# DMB.net
KiCad netlist of a schematic drawn in Altium Designer
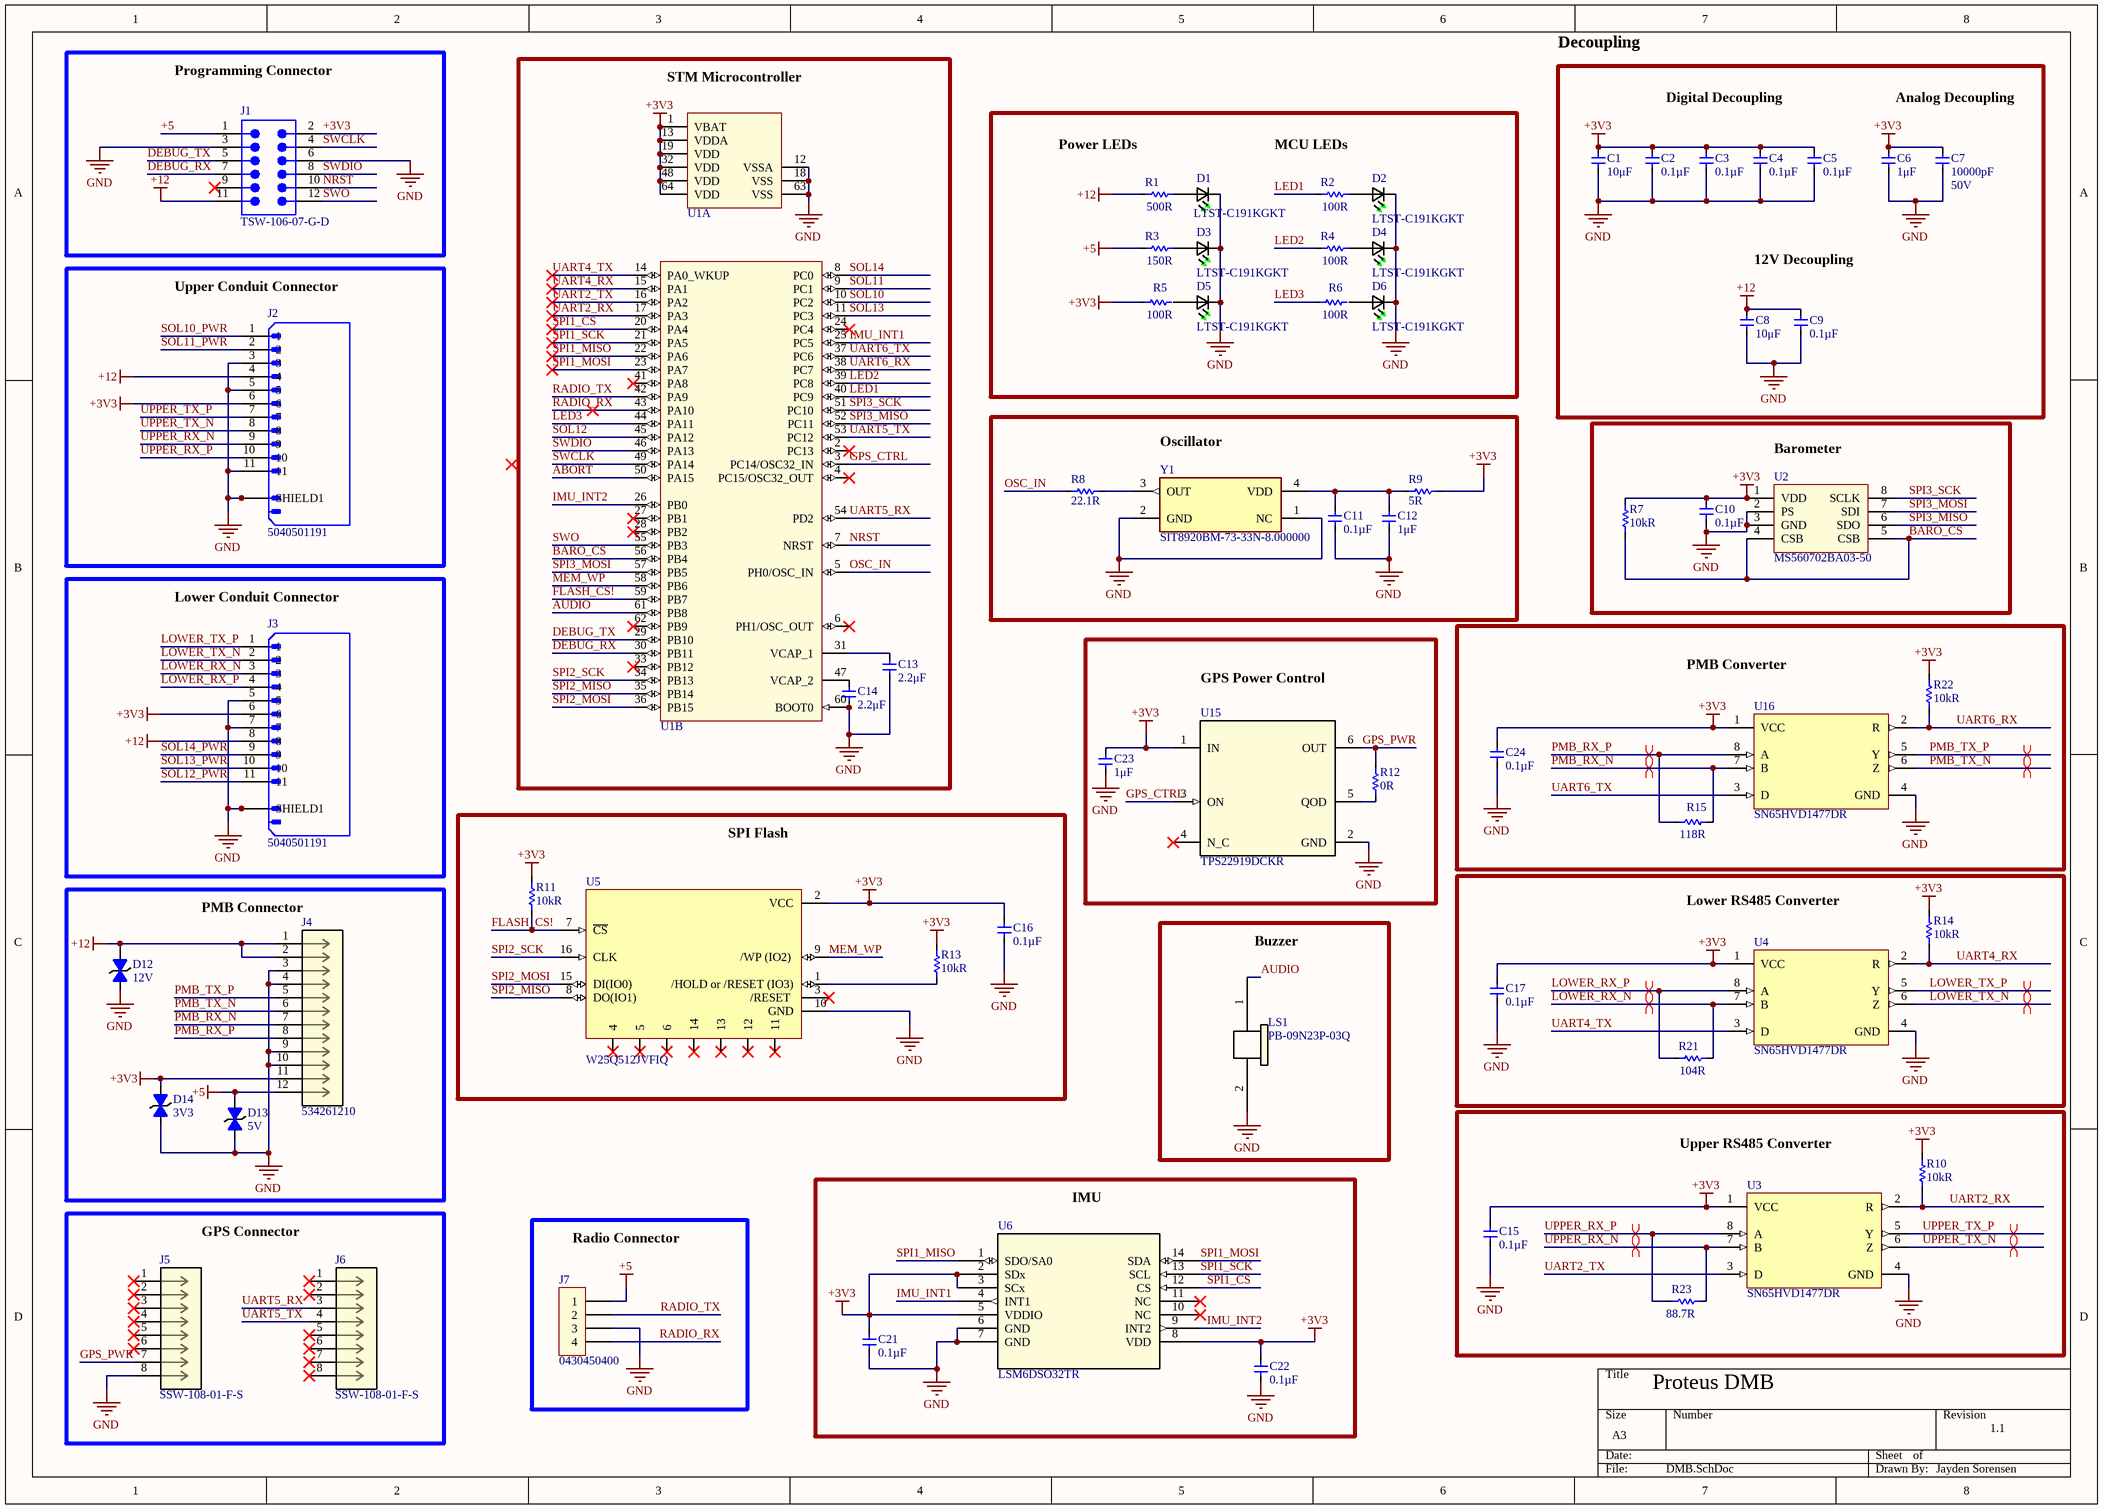
[diagram p0: DMB.SchDoc]

(export (version "E")
  (design (tool "Eeschema 10.0.6"))
  (components
    (comp (ref "C1")
      (value "10μF")
      (footprint "0603")
      (description "CAP CER 10UF 10V X5R 0603")
      (libsource (lib "BioRocketSchematics") (part "CL10A106MP8NNNC"))
    )
    (comp (ref "C2")
      (value "CGA3E2X7R1E104K080AA")
      (footprint "0603")
      (description "CAP CER 0.1UF 25V X7R 0603")
      (fields
        (field (name "MANUFACTURER") "TDK Corporation")
        (field (name "TOLERANCE") "±10%")
        (field (name "CAPACITANCE") "0.1µF")
      )
      (libsource (lib "BioRocketSchematics") (part "CGA3E2X7R1E104K080AA"))
    )
    (comp (ref "C3")
      (value "CGA3E2X7R1E104K080AA")
      (footprint "0603")
      (description "CAP CER 0.1UF 25V X7R 0603")
      (fields
        (field (name "MANUFACTURER") "TDK Corporation")
        (field (name "TOLERANCE") "±10%")
        (field (name "CAPACITANCE") "0.1µF")
      )
      (libsource (lib "BioRocketSchematics") (part "CGA3E2X7R1E104K080AA"))
    )
    (comp (ref "C4")
      (value "CGA3E2X7R1E104K080AA")
      (footprint "0603")
      (description "CAP CER 0.1UF 25V X7R 0603")
      (fields
        (field (name "MANUFACTURER") "TDK Corporation")
        (field (name "TOLERANCE") "±10%")
        (field (name "CAPACITANCE") "0.1µF")
      )
      (libsource (lib "BioRocketSchematics") (part "CGA3E2X7R1E104K080AA"))
    )
    (comp (ref "C5")
      (value "CGA3E2X7R1E104K080AA")
      (footprint "0603")
      (description "CAP CER 0.1UF 25V X7R 0603")
      (fields
        (field (name "MANUFACTURER") "TDK Corporation")
        (field (name "TOLERANCE") "±10%")
        (field (name "CAPACITANCE") "0.1µF")
      )
      (libsource (lib "BioRocketSchematics") (part "CGA3E2X7R1E104K080AA"))
    )
    (comp (ref "C6")
      (value "1μF")
      (footprint "0603")
      (description "CAP CER 1UF 10V X5R 0603")
      (libsource (lib "BioRocketSchematics") (part "CL10A105KP8NNNC"))
    )
    (comp (ref "C7")
      (value "CGA3E2X7R1H103K080AA")
      (footprint "0603")
      (description "CAP CER 10000PF 50V X7R 0603")
      (fields
        (field (name "MANUFACTURER") "TDK Corporation")
        (field (name "TOLERANCE") "±10%")
        (field (name "CAPACITANCE") "10000pF")
        (field (name "VOLTAGE - RATED") "50V")
      )
      (libsource (lib "BioRocketSchematics") (part "CGA3E2X7R1H103K080AA"))
    )
    (comp (ref "C8")
      (value "10μF")
      (footprint "0603")
      (description "CAP CER 10UF 10V X5R 0603")
      (libsource (lib "BioRocketSchematics") (part "CL10A106MP8NNNC"))
    )
    (comp (ref "C9")
      (value "CGA3E2X7R1E104K080AA")
      (footprint "0603")
      (description "CAP CER 0.1UF 25V X7R 0603")
      (fields
        (field (name "MANUFACTURER") "TDK Corporation")
        (field (name "TOLERANCE") "±10%")
        (field (name "CAPACITANCE") "0.1µF")
      )
      (libsource (lib "BioRocketSchematics") (part "CGA3E2X7R1E104K080AA"))
    )
    (comp (ref "C10")
      (value "CGA3E2X7R1E104K080AA")
      (footprint "0603")
      (description "CAP CER 0.1UF 25V X7R 0603")
      (fields
        (field (name "MANUFACTURER") "TDK Corporation")
        (field (name "TOLERANCE") "±10%")
        (field (name "CAPACITANCE") "0.1µF")
      )
      (libsource (lib "BioRocketSchematics") (part "CGA3E2X7R1E104K080AA"))
    )
    (comp (ref "C11")
      (value "CGA3E2X7R1E104K080AA")
      (footprint "0603")
      (description "CAP CER 0.1UF 25V X7R 0603")
      (fields
        (field (name "MANUFACTURER") "TDK Corporation")
        (field (name "TOLERANCE") "±10%")
        (field (name "CAPACITANCE") "0.1µF")
      )
      (libsource (lib "BioRocketSchematics") (part "CGA3E2X7R1E104K080AA"))
    )
    (comp (ref "C12")
      (value "1μF")
      (footprint "0603")
      (description "CAP CER 1UF 10V X5R 0603")
      (libsource (lib "BioRocketSchematics") (part "CL10A105KP8NNNC"))
    )
    (comp (ref "C13")
      (value "2.2μF")
      (footprint "0603")
      (description "CAP CER 2.2UF 16V X5R 0603")
      (libsource (lib "BioRocketSchematics") (part "C1608X5R1C225K080AB"))
    )
    (comp (ref "C14")
      (value "2.2μF")
      (footprint "0603")
      (description "CAP CER 2.2UF 16V X5R 0603")
      (libsource (lib "BioRocketSchematics") (part "C1608X5R1C225K080AB"))
    )
    (comp (ref "C15")
      (value "CGA3E2X7R1E104K080AA")
      (footprint "0603")
      (description "CAP CER 0.1UF 25V X7R 0603")
      (fields
        (field (name "MANUFACTURER") "TDK Corporation")
        (field (name "TOLERANCE") "±10%")
        (field (name "CAPACITANCE") "0.1µF")
      )
      (libsource (lib "BioRocketSchematics") (part "CGA3E2X7R1E104K080AA"))
    )
    (comp (ref "C16")
      (value "CGA3E2X7R1E104K080AA")
      (footprint "0603")
      (description "CAP CER 0.1UF 25V X7R 0603")
      (fields
        (field (name "MANUFACTURER") "TDK Corporation")
        (field (name "TOLERANCE") "±10%")
        (field (name "CAPACITANCE") "0.1µF")
      )
      (libsource (lib "BioRocketSchematics") (part "CGA3E2X7R1E104K080AA"))
    )
    (comp (ref "C17")
      (value "CGA3E2X7R1E104K080AA")
      (footprint "0603")
      (description "CAP CER 0.1UF 25V X7R 0603")
      (fields
        (field (name "MANUFACTURER") "TDK Corporation")
        (field (name "TOLERANCE") "±10%")
        (field (name "CAPACITANCE") "0.1µF")
      )
      (libsource (lib "BioRocketSchematics") (part "CGA3E2X7R1E104K080AA"))
    )
    (comp (ref "C21")
      (value "CGA3E2X7R1E104K080AA")
      (footprint "0603")
      (description "CAP CER 0.1UF 25V X7R 0603")
      (fields
        (field (name "MANUFACTURER") "TDK Corporation")
        (field (name "TOLERANCE") "±10%")
        (field (name "CAPACITANCE") "0.1µF")
      )
      (libsource (lib "BioRocketSchematics") (part "CGA3E2X7R1E104K080AA"))
    )
    (comp (ref "C22")
      (value "CGA3E2X7R1E104K080AA")
      (footprint "0603")
      (description "CAP CER 0.1UF 25V X7R 0603")
      (fields
        (field (name "MANUFACTURER") "TDK Corporation")
        (field (name "TOLERANCE") "±10%")
        (field (name "CAPACITANCE") "0.1µF")
      )
      (libsource (lib "BioRocketSchematics") (part "CGA3E2X7R1E104K080AA"))
    )
    (comp (ref "C23")
      (value "1μF")
      (footprint "0603")
      (description "CAP CER 1UF 10V X5R 0603")
      (libsource (lib "BioRocketSchematics") (part "CL10A105KP8NNNC"))
    )
    (comp (ref "C24")
      (value "CGA3E2X7R1E104K080AA")
      (footprint "0603")
      (description "CAP CER 0.1UF 25V X7R 0603")
      (fields
        (field (name "MANUFACTURER") "TDK Corporation")
        (field (name "TOLERANCE") "±10%")
        (field (name "CAPACITANCE") "0.1µF")
      )
      (libsource (lib "BioRocketSchematics") (part "CGA3E2X7R1E104K080AA"))
    )
    (comp (ref "D1")
      (value "LTST-C191KGKT")
      (footprint "LED_LTST-C191KGKT_LTO")
      (description "LED GREEN CLEAR SMD 0603")
      (libsource (lib "BioRocketSchematics") (part "LTST-C191KGKT"))
    )
    (comp (ref "D2")
      (value "LTST-C191KGKT")
      (footprint "LED_LTST-C191KGKT_LTO")
      (description "LED GREEN CLEAR SMD 0603")
      (libsource (lib "BioRocketSchematics") (part "LTST-C191KGKT"))
    )
    (comp (ref "D3")
      (value "LTST-C191KGKT")
      (footprint "LED_LTST-C191KGKT_LTO")
      (description "LED GREEN CLEAR SMD 0603")
      (libsource (lib "BioRocketSchematics") (part "LTST-C191KGKT"))
    )
    (comp (ref "D4")
      (value "LTST-C191KGKT")
      (footprint "LED_LTST-C191KGKT_LTO")
      (description "LED GREEN CLEAR SMD 0603")
      (libsource (lib "BioRocketSchematics") (part "LTST-C191KGKT"))
    )
    (comp (ref "D5")
      (value "LTST-C191KGKT")
      (footprint "LED_LTST-C191KGKT_LTO")
      (description "LED GREEN CLEAR SMD 0603")
      (libsource (lib "BioRocketSchematics") (part "LTST-C191KGKT"))
    )
    (comp (ref "D6")
      (value "LTST-C191KGKT")
      (footprint "LED_LTST-C191KGKT_LTO")
      (description "LED GREEN CLEAR SMD 0603")
      (libsource (lib "BioRocketSchematics") (part "LTST-C191KGKT"))
    )
    (comp (ref "D12")
      (value "12V")
      (footprint "SOD-323-2")
      (description "TVS 12V Working, 23V Clamp - ESD Suppressor Diode TVS Bi-Dir 12V Automotive 2-Pin SOD-323 T/R")
      (fields
        (field (name "MANUFACTURER") "Littelfuse")
        (field (name "MANUFACTURER PART NUMBER") "SD12C-01FTG")
      )
      (libsource (lib "BioRocketSchematics") (part "SD12C-01FTG"))
    )
    (comp (ref "D13")
      (value "5V")
      (footprint "SOD-323-2")
      (description "TVS 5V Working, 19.6V Clamp - ESD Protection Diodes / TVS Diodes 2.5pF 25A BI for Surge Protection")
      (libsource (lib "BioRocketSchematics") (part "SP4021-01FTG-C"))
    )
    (comp (ref "D14")
      (value "3V3")
      (footprint "SOD-323-2")
      (description "TVS 3.3V Working, 10.9V Clamp - 10.9V (Typ) Clamp 43A (8/20µs) Ipp Tvs Diode Surface Mount SOD-323")
      (fields
        (field (name "MANUFACTURER") "Bourns")
        (field (name "MANUFACTURER PART NUMBER") "CDSOD323-T03SC")
      )
      (libsource (lib "BioRocketSchematics") (part "CDSOD323-T03SC"))
    )
    (comp (ref "J1")
      (value "TSW-106-07-G-D")
      (footprint "SMTC-TSW-106-07-X-D")
      (description "0.025\" SQ Post Header, Through-hole, Vertical, -55 to 125 degC, 2.54 mm Pitch, 12-Pin, Male, RoHS")
      (fields (field (name "MANUFACTURER") "Samtec"))
      (libsource (lib "Altium Content Vault") (part "SMTC-TSW-106-07-X-D"))
    )
    (comp (ref "J2")
      (value "5040501191")
      (footprint "MOLEX_5040501191")
      (description "11-pin Pico Lock Right-Angle PCB header")
      (libsource (lib "BioRocketSchematics") (part "5040501191"))
    )
    (comp (ref "J3")
      (value "5040501191")
      (footprint "MOLEX_5040501191")
      (description "11-pin Pico Lock Right-Angle PCB header")
      (libsource (lib "BioRocketSchematics") (part "5040501191"))
    )
    (comp (ref "J4")
      (value "534261210")
      (footprint "2159321270")
      (description "CONN HEADER R/A 12POS 2.5MM")
      (libsource (lib "BioRocketSchematics") (part "534261210"))
    )
    (comp (ref "J5")
      (value "SSW-108-01-F-S")
      (footprint "CON8_1X8_TU_SSQ")
      (description "PCB Receptacle, Board-to-Board, 2.54 mm, 1 Rows, 8 Contacts")
      (libsource (lib "BioRocketSchematics") (part "SSW-108-01-F-S"))
    )
    (comp (ref "J6")
      (value "SSW-108-01-F-S")
      (footprint "CON8_1X8_TU_SSQ")
      (description "PCB Receptacle, Board-to-Board, 2.54 mm, 1 Rows, 8 Contacts")
      (libsource (lib "BioRocketSchematics") (part "SSW-108-01-F-S"))
    )
    (comp (ref "J7")
      (value "0430450400")
      (footprint "0430450400")
      (description "CONN HEADER R/A 4POS 3MM")
      (libsource (lib "BioRocketSchematics") (part "0430450400"))
    )
    (comp (ref "LS1")
      (value "PB-09N23P-03Q")
      (footprint "PB-09N23P-03Q")
      (description "Buzzers Indicator, Internally Driven Magnetic 3 V 30mA 2.7kHz 82dB @ 3V, 10cm Through Hole PC Pins")
      (libsource (lib "BioRocketSchematics") (part "PB-09N23P-03Q"))
    )
    (comp (ref "R1")
      (value "500R")
      (footprint "0603")
      (description "RES 500 OHM 0.1% 1/10W 0603")
      (libsource (lib "BioRocketSchematics") (part "RT0603BRD07500RL"))
    )
    (comp (ref "R2")
      (value "100R")
      (footprint "0603")
      (description "RES 500 OHM 0.1% 1/10W 0603")
      (libsource (lib "BioRocketSchematics") (part "RT0603BRD07500RL"))
    )
    (comp (ref "R3")
      (value "150R")
      (footprint "0603")
      (description "RES 150 OHM 1% 1/10W 0603")
      (libsource (lib "BioRocketSchematics") (part "RMCF0603FT150R"))
    )
    (comp (ref "R4")
      (value "100R")
      (footprint "0603")
      (description "RES 150 OHM 1% 1/10W 0603")
      (libsource (lib "BioRocketSchematics") (part "RMCF0603FT150R"))
    )
    (comp (ref "R5")
      (value "100R")
      (footprint "0603")
      (description "RES SMD 100 OHM 1% 1/10W 0603")
      (libsource (lib "BioRocketSchematics") (part "ERJ-3EKF1000V"))
    )
    (comp (ref "R6")
      (value "100R")
      (footprint "0603")
      (description "RES SMD 100 OHM 1% 1/10W 0603")
      (libsource (lib "BioRocketSchematics") (part "ERJ-3EKF1000V"))
    )
    (comp (ref "R7")
      (value "10kR")
      (footprint "0603")
      (description "RES SMD 10K OHM 5% 1/10W 0603")
      (libsource (lib "BioRocketSchematics") (part "ERJ-3GEYJ103V"))
    )
    (comp (ref "R8")
      (value "22.1R")
      (footprint "0603")
      (description "Thick Film Resistors - SMD 0603 22.1ohms 0.2W 1% AEC-Q200")
      (libsource (lib "BioRocketSchematics") (part "ERJ-P03F22R1V"))
    )
    (comp (ref "R9")
      (value "PWR2010W5R00JE")
      (footprint "BO_PWR2010")
      (description "Res Wirewound 2010 5 Ohm 5% 1/2W ±50ppm/°C Molded SMD SMD T/R")
      (fields
        (field (name "MANUFACTURER") "Bourns")
        (field (name "TOLERANCE") "5%")
        (field (name "RESISTANCE") "5R")
      )
      (libsource (lib "BioRocketSchematics") (part "PWR2010W5R00JE"))
    )
    (comp (ref "R10")
      (value "10kR")
      (footprint "0603")
      (description "RES SMD 10K OHM 5% 1/10W 0603")
      (libsource (lib "BioRocketSchematics") (part "ERJ-3GEYJ103V"))
    )
    (comp (ref "R11")
      (value "10kR")
      (footprint "0603")
      (description "RES SMD 10K OHM 5% 1/10W 0603")
      (libsource (lib "BioRocketSchematics") (part "ERJ-3GEYJ103V"))
    )
    (comp (ref "R12")
      (value "0R")
      (footprint "0603")
      (description "Thick Film Resistors - SMD 0 Ohms 100 mW 0603 5%")
      (libsource (lib "BioRocketSchematics") (part "RC0603JR-070RL"))
    )
    (comp (ref "R13")
      (value "10kR")
      (footprint "0603")
      (description "RES SMD 10K OHM 5% 1/10W 0603")
      (libsource (lib "BioRocketSchematics") (part "ERJ-3GEYJ103V"))
    )
    (comp (ref "R14")
      (value "10kR")
      (footprint "0603")
      (description "RES SMD 10K OHM 5% 1/10W 0603")
      (libsource (lib "BioRocketSchematics") (part "ERJ-3GEYJ103V"))
    )
    (comp (ref "R15")
      (value "118R")
      (footprint "0603")
      (description "RES SMD 118 OHM 1% 1/10W 0603")
      (libsource (lib "BioRocketSchematics") (part "ERJ-3EKF1180V"))
    )
    (comp (ref "R21")
      (value "104R")
      (footprint "0603")
      (description "RES SMD 104 OHM 0.1% 1/10W 0603")
      (libsource (lib "BioRocketSchematics") (part "RT0603BRD07104RL"))
    )
    (comp (ref "R22")
      (value "10kR")
      (footprint "0603")
      (description "RES SMD 10K OHM 5% 1/10W 0603")
      (libsource (lib "BioRocketSchematics") (part "ERJ-3GEYJ103V"))
    )
    (comp (ref "R23")
      (value "88.7R")
      (footprint "0603")
      (description "RES SMD 88.7 OHM 1% 1/10W 0603")
      (libsource (lib "BioRocketSchematics") (part "CRCW060388R7FKEA"))
    )
    (comp (ref "U1")
      (value "STM32F405RGT6")
      (footprint "TSQFP50P1200X1200X160-64N")
      (description "IC MCU 32BIT 1MB FLASH 64LQFP")
      (fields (field (name "MANUFACTURER") "STMicroelectronics"))
      (libsource (lib "BioRocketSchematics") (part "STM32F405RGT6"))
    )
    (comp (ref "U2")
      (value "MS560702BA03-50")
      (footprint "TECO-MS560702BA03-50_V")
      (description "BAROMETRIC PRESSURE SENSOR")
      (libsource (lib "BioRocketSchematics") (part "MS560702BA03-50"))
    )
    (comp (ref "U3")
      (value "SN65HVD1477DR")
      (footprint "SOIC127P600X175-8N")
      (description "3.3V, Full-Duplex RS-485, 16kV IEC ESD, 50Mbps data rate, No Enables 8-SOIC -40 to 125")
      (libsource (lib "BioRocketSchematics") (part "SN65HVD1477DR"))
    )
    (comp (ref "U4")
      (value "SN65HVD1477DR")
      (footprint "SOIC127P600X175-8N")
      (description "3.3V, Full-Duplex RS-485, 16kV IEC ESD, 50Mbps data rate, No Enables 8-SOIC -40 to 125")
      (libsource (lib "BioRocketSchematics") (part "SN65HVD1477DR"))
    )
    (comp (ref "U5")
      (value "W25Q512JVFIQ")
      (footprint "SOIC127P1030X265-16N")
      (description "IC Flash 512MBIT Spi/quad 16SOIC")
      (libsource (lib "BioRocketSchematics") (part "W25Q512JVFIQ"))
    )
    (comp (ref "U6")
      (value "LSM6DSO32TR")
      (footprint "LSM6DSO32TR")
      (description "6-axis IMU, 3-axis accelerometer and 3-axis gyroscope")
      (libsource (lib "BioRocketSchematics") (part "LSM6DSO32TR"))
    )
    (comp (ref "U15")
      (value "TPS22919DCKR")
      (footprint "SC-70-6")
      (description "5.5-V, 1.5-A, 90-mΩ load switch with adj. output discharge 6-SC70 -40 to 105")
      (libsource (lib "BioRocketSchematics") (part "TPS22919DCKR"))
    )
    (comp (ref "U16")
      (value "SN65HVD1477DR")
      (footprint "SOIC127P600X175-8N")
      (description "3.3V, Full-Duplex RS-485, 16kV IEC ESD, 50Mbps data rate, No Enables 8-SOIC -40 to 125")
      (libsource (lib "BioRocketSchematics") (part "SN65HVD1477DR"))
    )
    (comp (ref "Y1")
      (value "SIT8920BM-73-33N-8.000000")
      (footprint "FP-SIT8920BM-73-33N-8_000-MFG")
      (description "MEMS OSC XO 8.0000MHZ LVCM LVTTL")
      (libsource (lib "Altium Content Vault") (part "f8eed742da43ac8d7009b5f8d825914"))
    )
  )
  (nets
    (net (code "1") (name "+3V3") (class "Default")
      (node (ref "C1") (pin "2") (pinfunction "2_2") (pintype "passive"))
      (node (ref "C10") (pin "2") (pinfunction "2_2") (pintype "passive"))
      (node (ref "C15") (pin "2") (pinfunction "2_2") (pintype "passive"))
      (node (ref "C16") (pin "2") (pinfunction "2_2") (pintype "passive"))
      (node (ref "C17") (pin "2") (pinfunction "2_2") (pintype "passive"))
      (node (ref "C2") (pin "2") (pinfunction "2_2") (pintype "passive"))
      (node (ref "C21") (pin "2") (pinfunction "2_2") (pintype "passive"))
      (node (ref "C22") (pin "2") (pinfunction "2_2") (pintype "passive"))
      (node (ref "C23") (pin "2") (pinfunction "2_2") (pintype "passive"))
      (node (ref "C24") (pin "2") (pinfunction "2_2") (pintype "passive"))
      (node (ref "C3") (pin "2") (pinfunction "2_2") (pintype "passive"))
      (node (ref "C4") (pin "2") (pinfunction "2_2") (pintype "passive"))
      (node (ref "C5") (pin "2") (pinfunction "2_2") (pintype "passive"))
      (node (ref "C6") (pin "2") (pinfunction "2_2") (pintype "passive"))
      (node (ref "C7") (pin "2") (pinfunction "2_2") (pintype "passive"))
      (node (ref "D14") (pin "1") (pinfunction "1_1") (pintype "power_in"))
      (node (ref "J1") (pin "2") (pinfunction "2_2") (pintype "passive"))
      (node (ref "J2") (pin "6") (pinfunction "6_6") (pintype "passive"))
      (node (ref "J3") (pin "6") (pinfunction "6_6") (pintype "passive"))
      (node (ref "J4") (pin "11") (pinfunction "11_11") (pintype "passive"))
      (node (ref "R10") (pin "2") (pinfunction "2_2") (pintype "passive"))
      (node (ref "R11") (pin "2") (pinfunction "2_2") (pintype "passive"))
      (node (ref "R13") (pin "2") (pinfunction "2_2") (pintype "passive"))
      (node (ref "R14") (pin "2") (pinfunction "2_2") (pintype "passive"))
      (node (ref "R22") (pin "2") (pinfunction "2_2") (pintype "passive"))
      (node (ref "R5") (pin "1") (pinfunction "1_1") (pintype "passive"))
      (node (ref "R7") (pin "2") (pinfunction "2_2") (pintype "passive"))
      (node (ref "R9") (pin "2") (pinfunction "2_2") (pintype "passive"))
      (node (ref "U1") (pin "1") (pinfunction "VBAT_1") (pintype "power_in"))
      (node (ref "U1") (pin "13") (pinfunction "VDDA_13") (pintype "power_in"))
      (node (ref "U1") (pin "19") (pinfunction "VDD_19") (pintype "power_in"))
      (node (ref "U1") (pin "32") (pinfunction "VDD_32") (pintype "power_in"))
      (node (ref "U1") (pin "48") (pinfunction "VDD_48") (pintype "power_in"))
      (node (ref "U1") (pin "64") (pinfunction "VDD_64") (pintype "power_in"))
      (node (ref "U15") (pin "1") (pinfunction "IN_1") (pintype "power_in"))
      (node (ref "U16") (pin "1") (pinfunction "VCC_1") (pintype "passive"))
      (node (ref "U2") (pin "1") (pinfunction "VDD_1") (pintype "power_in"))
      (node (ref "U3") (pin "1") (pinfunction "VCC_1") (pintype "passive"))
      (node (ref "U4") (pin "1") (pinfunction "VCC_1") (pintype "passive"))
      (node (ref "U5") (pin "2") (pinfunction "VCC_2") (pintype "passive"))
      (node (ref "U6") (pin "2") (pinfunction "SDx_2") (pintype "passive"))
      (node (ref "U6") (pin "3") (pinfunction "SCx_3") (pintype "passive"))
      (node (ref "U6") (pin "5") (pinfunction "VDDIO_5") (pintype "power_in"))
      (node (ref "U6") (pin "8") (pinfunction "VDD_8") (pintype "power_in"))
    )
    (net (code "2") (name "+5") (class "Default")
      (node (ref "D13") (pin "2") (pinfunction "2_2") (pintype "power_in"))
      (node (ref "J1") (pin "1") (pinfunction "1_1") (pintype "passive"))
      (node (ref "J4") (pin "12") (pinfunction "12_12") (pintype "passive"))
      (node (ref "J7") (pin "1") (pinfunction "1_1") (pintype "passive"))
      (node (ref "R3") (pin "1") (pinfunction "1_1") (pintype "passive"))
    )
    (net (code "3") (name "+12") (class "Default")
      (node (ref "C8") (pin "2") (pinfunction "2_2") (pintype "passive"))
      (node (ref "C9") (pin "2") (pinfunction "2_2") (pintype "passive"))
      (node (ref "D12") (pin "2") (pinfunction "2_2") (pintype "power_in"))
      (node (ref "J1") (pin "11") (pinfunction "11_11") (pintype "passive"))
      (node (ref "J2") (pin "4") (pinfunction "4_4") (pintype "passive"))
      (node (ref "J3") (pin "8") (pinfunction "8_8") (pintype "passive"))
      (node (ref "J4") (pin "1") (pinfunction "1_1") (pintype "passive"))
      (node (ref "J4") (pin "2") (pinfunction "2_2") (pintype "passive"))
      (node (ref "R1") (pin "1") (pinfunction "1_1") (pintype "passive"))
    )
    (net (code "4") (name "/ABORT") (class "Default")
      (node (ref "U1") (pin "50") (pinfunction "PA15_50") (pintype "bidirectional"))
    )
    (net (code "5") (name "/AUDIO") (class "Default")
      (node (ref "LS1") (pin "1") (pinfunction "1_1") (pintype "passive"))
      (node (ref "U1") (pin "61") (pinfunction "PB8_61") (pintype "bidirectional"))
    )
    (net (code "6") (name "/BARO_~{CS}") (class "Default")
      (node (ref "R7") (pin "1") (pinfunction "1_1") (pintype "passive"))
      (node (ref "U1") (pin "56") (pinfunction "PB4_56") (pintype "bidirectional"))
      (node (ref "U2") (pin "4") (pinfunction "CSB_4") (pintype "passive"))
      (node (ref "U2") (pin "5") (pinfunction "CSB_5") (pintype "passive"))
    )
    (net (code "7") (name "/DEBUG_RX") (class "Default")
      (node (ref "J1") (pin "7") (pinfunction "7_7") (pintype "passive"))
      (node (ref "U1") (pin "30") (pinfunction "PB11_30") (pintype "bidirectional"))
    )
    (net (code "8") (name "/DEBUG_TX") (class "Default")
      (node (ref "J1") (pin "5") (pinfunction "5_5") (pintype "passive"))
      (node (ref "U1") (pin "29") (pinfunction "PB10_29") (pintype "bidirectional"))
    )
    (net (code "9") (name "/FLASH_CS!") (class "Default")
      (node (ref "R11") (pin "1") (pinfunction "1_1") (pintype "passive"))
      (node (ref "U1") (pin "59") (pinfunction "PB7_59") (pintype "bidirectional"))
      (node (ref "U5") (pin "7") (pinfunction "~{CS}_7") (pintype "input"))
    )
    (net (code "10") (name "/GPS_CTRL") (class "Default")
      (node (ref "U1") (pin "3") (pinfunction "PC14/OSC32_IN_3") (pintype "bidirectional"))
      (node (ref "U15") (pin "3") (pinfunction "ON_3") (pintype "input"))
    )
    (net (code "11") (name "/GPS_PWR") (class "Default")
      (node (ref "J5") (pin "7") (pinfunction "7_7") (pintype "passive"))
      (node (ref "R12") (pin "2") (pinfunction "2_2") (pintype "passive"))
      (node (ref "U15") (pin "6") (pinfunction "OUT_6") (pintype "power_in"))
    )
    (net (code "12") (name "/IMU_INT1") (class "Default")
      (node (ref "U1") (pin "25") (pinfunction "PC5_25") (pintype "bidirectional"))
      (node (ref "U6") (pin "4") (pinfunction "INT1_4") (pintype "output"))
    )
    (net (code "13") (name "/IMU_INT2") (class "Default")
      (node (ref "U1") (pin "26") (pinfunction "PB0_26") (pintype "bidirectional"))
      (node (ref "U6") (pin "9") (pinfunction "INT2_9") (pintype "output"))
    )
    (net (code "14") (name "/LED1") (class "Default")
      (node (ref "R2") (pin "1") (pinfunction "1_1") (pintype "passive"))
      (node (ref "U1") (pin "40") (pinfunction "PC9_40") (pintype "bidirectional"))
    )
    (net (code "15") (name "/LED2") (class "Default")
      (node (ref "R4") (pin "1") (pinfunction "1_1") (pintype "passive"))
      (node (ref "U1") (pin "39") (pinfunction "PC8_39") (pintype "bidirectional"))
    )
    (net (code "16") (name "/LED3") (class "Default")
      (node (ref "R6") (pin "1") (pinfunction "1_1") (pintype "passive"))
      (node (ref "U1") (pin "44") (pinfunction "PA11_44") (pintype "bidirectional"))
    )
    (net (code "17") (name "/LOWER_RX_N") (class "Default")
      (node (ref "J3") (pin "3") (pinfunction "3_3") (pintype "passive"))
      (node (ref "R21") (pin "2") (pinfunction "2_2") (pintype "passive"))
      (node (ref "U4") (pin "7") (pinfunction "B_7") (pintype "input"))
    )
    (net (code "18") (name "/LOWER_RX_P") (class "Default")
      (node (ref "J3") (pin "4") (pinfunction "4_4") (pintype "passive"))
      (node (ref "R21") (pin "1") (pinfunction "1_1") (pintype "passive"))
      (node (ref "U4") (pin "8") (pinfunction "A_8") (pintype "input"))
    )
    (net (code "19") (name "/LOWER_TX_N") (class "Default")
      (node (ref "J3") (pin "2") (pinfunction "2_2") (pintype "passive"))
      (node (ref "U4") (pin "6") (pinfunction "Z_6") (pintype "output"))
    )
    (net (code "20") (name "/LOWER_TX_P") (class "Default")
      (node (ref "J3") (pin "1") (pinfunction "1_1") (pintype "passive"))
      (node (ref "U4") (pin "5") (pinfunction "Y_5") (pintype "output"))
    )
    (net (code "21") (name "/MEM_WP") (class "Default")
      (node (ref "U1") (pin "58") (pinfunction "PB6_58") (pintype "bidirectional"))
      (node (ref "U5") (pin "9") (pinfunction "/WP_(IO2)_9") (pintype "bidirectional"))
    )
    (net (code "22") (name "/NRST") (class "Default")
      (node (ref "J1") (pin "10") (pinfunction "10_10") (pintype "passive"))
      (node (ref "U1") (pin "7") (pinfunction "NRST_7") (pintype "bidirectional"))
    )
    (net (code "23") (name "/OSC_IN") (class "Default")
      (node (ref "R8") (pin "1") (pinfunction "1_1") (pintype "passive"))
      (node (ref "U1") (pin "5") (pinfunction "PH0/OSC_IN_5") (pintype "bidirectional"))
    )
    (net (code "24") (name "/PMB_RX_N") (class "Default")
      (node (ref "J4") (pin "7") (pinfunction "7_7") (pintype "passive"))
      (node (ref "R15") (pin "2") (pinfunction "2_2") (pintype "passive"))
      (node (ref "U16") (pin "7") (pinfunction "B_7") (pintype "input"))
    )
    (net (code "25") (name "/PMB_RX_P") (class "Default")
      (node (ref "J4") (pin "8") (pinfunction "8_8") (pintype "passive"))
      (node (ref "R15") (pin "1") (pinfunction "1_1") (pintype "passive"))
      (node (ref "U16") (pin "8") (pinfunction "A_8") (pintype "input"))
    )
    (net (code "26") (name "/PMB_TX_N") (class "Default")
      (node (ref "J4") (pin "6") (pinfunction "6_6") (pintype "passive"))
      (node (ref "U16") (pin "6") (pinfunction "Z_6") (pintype "output"))
    )
    (net (code "27") (name "/PMB_TX_P") (class "Default")
      (node (ref "J4") (pin "5") (pinfunction "5_5") (pintype "passive"))
      (node (ref "U16") (pin "5") (pinfunction "Y_5") (pintype "output"))
    )
    (net (code "28") (name "/RADIO_RX") (class "Default")
      (node (ref "J7") (pin "4") (pinfunction "4_4") (pintype "passive"))
      (node (ref "U1") (pin "43") (pinfunction "PA10_43") (pintype "bidirectional"))
    )
    (net (code "29") (name "/RADIO_TX") (class "Default")
      (node (ref "J7") (pin "2") (pinfunction "2_2") (pintype "passive"))
      (node (ref "U1") (pin "42") (pinfunction "PA9_42") (pintype "bidirectional"))
    )
    (net (code "30") (name "/SOL10") (class "Default")
      (node (ref "U1") (pin "10") (pinfunction "PC2_10") (pintype "bidirectional"))
    )
    (net (code "31") (name "/SOL10_PWR") (class "Default")
      (node (ref "J2") (pin "1") (pinfunction "1_1") (pintype "passive"))
    )
    (net (code "32") (name "/SOL11") (class "Default")
      (node (ref "U1") (pin "9") (pinfunction "PC1_9") (pintype "bidirectional"))
    )
    (net (code "33") (name "/SOL11_PWR") (class "Default")
      (node (ref "J2") (pin "2") (pinfunction "2_2") (pintype "passive"))
    )
    (net (code "34") (name "/SOL12") (class "Default")
      (node (ref "U1") (pin "45") (pinfunction "PA12_45") (pintype "bidirectional"))
    )
    (net (code "35") (name "/SOL12_PWR") (class "Default")
      (node (ref "J3") (pin "11") (pinfunction "11_11") (pintype "passive"))
    )
    (net (code "36") (name "/SOL13") (class "Default")
      (node (ref "U1") (pin "11") (pinfunction "PC3_11") (pintype "bidirectional"))
    )
    (net (code "37") (name "/SOL13_PWR") (class "Default")
      (node (ref "J3") (pin "10") (pinfunction "10_10") (pintype "passive"))
    )
    (net (code "38") (name "/SOL14") (class "Default")
      (node (ref "U1") (pin "8") (pinfunction "PC0_8") (pintype "bidirectional"))
    )
    (net (code "39") (name "/SOL14_PWR") (class "Default")
      (node (ref "J3") (pin "9") (pinfunction "9_9") (pintype "passive"))
    )
    (net (code "40") (name "/SPI1_CS") (class "Default")
      (node (ref "U1") (pin "20") (pinfunction "PA4_20") (pintype "bidirectional"))
      (node (ref "U6") (pin "12") (pinfunction "CS_12") (pintype "input"))
    )
    (net (code "41") (name "/SPI1_MISO") (class "Default")
      (node (ref "U1") (pin "22") (pinfunction "PA6_22") (pintype "bidirectional"))
      (node (ref "U6") (pin "1") (pinfunction "SDO/SA0_1") (pintype "bidirectional"))
    )
    (net (code "42") (name "/SPI1_MOSI") (class "Default")
      (node (ref "U1") (pin "23") (pinfunction "PA7_23") (pintype "bidirectional"))
      (node (ref "U6") (pin "14") (pinfunction "SDA_14") (pintype "bidirectional"))
    )
    (net (code "43") (name "/SPI1_SCK") (class "Default")
      (node (ref "U1") (pin "21") (pinfunction "PA5_21") (pintype "bidirectional"))
      (node (ref "U6") (pin "13") (pinfunction "SCL_13") (pintype "input"))
    )
    (net (code "44") (name "/SPI2_MISO") (class "Default")
      (node (ref "U1") (pin "35") (pinfunction "PB14_35") (pintype "bidirectional"))
      (node (ref "U5") (pin "8") (pinfunction "DO(IO1)_8") (pintype "bidirectional"))
    )
    (net (code "45") (name "/SPI2_MOSI") (class "Default")
      (node (ref "U1") (pin "36") (pinfunction "PB15_36") (pintype "bidirectional"))
      (node (ref "U5") (pin "15") (pinfunction "DI(IO0)_15") (pintype "bidirectional"))
    )
    (net (code "46") (name "/SPI2_SCK") (class "Default")
      (node (ref "U1") (pin "34") (pinfunction "PB13_34") (pintype "bidirectional"))
      (node (ref "U5") (pin "16") (pinfunction "CLK_16") (pintype "input"))
    )
    (net (code "47") (name "/SPI3_MISO") (class "Default")
      (node (ref "U1") (pin "52") (pinfunction "PC11_52") (pintype "bidirectional"))
      (node (ref "U2") (pin "6") (pinfunction "SDO_6") (pintype "passive"))
    )
    (net (code "48") (name "/SPI3_MOSI") (class "Default")
      (node (ref "U1") (pin "57") (pinfunction "PB5_57") (pintype "bidirectional"))
      (node (ref "U2") (pin "7") (pinfunction "SDI_7") (pintype "passive"))
    )
    (net (code "49") (name "/SPI3_SCK") (class "Default")
      (node (ref "U1") (pin "51") (pinfunction "PC10_51") (pintype "bidirectional"))
      (node (ref "U2") (pin "8") (pinfunction "SCLK_8") (pintype "passive"))
    )
    (net (code "50") (name "/SWCLK") (class "Default")
      (node (ref "J1") (pin "4") (pinfunction "4_4") (pintype "passive"))
      (node (ref "U1") (pin "49") (pinfunction "PA14_49") (pintype "bidirectional"))
    )
    (net (code "51") (name "/SWDIO") (class "Default")
      (node (ref "J1") (pin "8") (pinfunction "8_8") (pintype "passive"))
      (node (ref "U1") (pin "46") (pinfunction "PA13_46") (pintype "bidirectional"))
    )
    (net (code "52") (name "/SWO") (class "Default")
      (node (ref "J1") (pin "12") (pinfunction "12_12") (pintype "passive"))
      (node (ref "U1") (pin "55") (pinfunction "PB3_55") (pintype "bidirectional"))
    )
    (net (code "53") (name "/UART2_RX") (class "Default")
      (node (ref "R10") (pin "1") (pinfunction "1_1") (pintype "passive"))
      (node (ref "U1") (pin "17") (pinfunction "PA3_17") (pintype "bidirectional"))
      (node (ref "U3") (pin "2") (pinfunction "R_2") (pintype "output"))
    )
    (net (code "54") (name "/UART2_TX") (class "Default")
      (node (ref "U1") (pin "16") (pinfunction "PA2_16") (pintype "bidirectional"))
      (node (ref "U3") (pin "3") (pinfunction "D_3") (pintype "input"))
    )
    (net (code "55") (name "/UART4_RX") (class "Default")
      (node (ref "R14") (pin "1") (pinfunction "1_1") (pintype "passive"))
      (node (ref "U1") (pin "15") (pinfunction "PA1_15") (pintype "bidirectional"))
      (node (ref "U4") (pin "2") (pinfunction "R_2") (pintype "output"))
    )
    (net (code "56") (name "/UART4_TX") (class "Default")
      (node (ref "U1") (pin "14") (pinfunction "PA0_WKUP_14") (pintype "bidirectional"))
      (node (ref "U4") (pin "3") (pinfunction "D_3") (pintype "input"))
    )
    (net (code "57") (name "/UART5_RX") (class "Default")
      (node (ref "J6") (pin "3") (pinfunction "3_3") (pintype "passive"))
      (node (ref "U1") (pin "54") (pinfunction "PD2_54") (pintype "bidirectional"))
    )
    (net (code "58") (name "/UART5_TX") (class "Default")
      (node (ref "J6") (pin "4") (pinfunction "4_4") (pintype "passive"))
      (node (ref "U1") (pin "53") (pinfunction "PC12_53") (pintype "bidirectional"))
    )
    (net (code "59") (name "/UART6_RX") (class "Default")
      (node (ref "R22") (pin "1") (pinfunction "1_1") (pintype "passive"))
      (node (ref "U1") (pin "38") (pinfunction "PC7_38") (pintype "bidirectional"))
      (node (ref "U16") (pin "2") (pinfunction "R_2") (pintype "output"))
    )
    (net (code "60") (name "/UART6_TX") (class "Default")
      (node (ref "U1") (pin "37") (pinfunction "PC6_37") (pintype "bidirectional"))
      (node (ref "U16") (pin "3") (pinfunction "D_3") (pintype "input"))
    )
    (net (code "61") (name "/UPPER_RX_N") (class "Default")
      (node (ref "J2") (pin "9") (pinfunction "9_9") (pintype "passive"))
      (node (ref "R23") (pin "2") (pinfunction "2_2") (pintype "passive"))
      (node (ref "U3") (pin "7") (pinfunction "B_7") (pintype "input"))
    )
    (net (code "62") (name "/UPPER_RX_P") (class "Default")
      (node (ref "J2") (pin "10") (pinfunction "10_10") (pintype "passive"))
      (node (ref "R23") (pin "1") (pinfunction "1_1") (pintype "passive"))
      (node (ref "U3") (pin "8") (pinfunction "A_8") (pintype "input"))
    )
    (net (code "63") (name "/UPPER_TX_N") (class "Default")
      (node (ref "J2") (pin "8") (pinfunction "8_8") (pintype "passive"))
      (node (ref "U3") (pin "6") (pinfunction "Z_6") (pintype "output"))
    )
    (net (code "64") (name "/UPPER_TX_P") (class "Default")
      (node (ref "J2") (pin "7") (pinfunction "7_7") (pintype "passive"))
      (node (ref "U3") (pin "5") (pinfunction "Y_5") (pintype "output"))
    )
    (net (code "65") (name "GND") (class "Default")
      (node (ref "C1") (pin "1") (pinfunction "1_1") (pintype "passive"))
      (node (ref "C10") (pin "1") (pinfunction "1_1") (pintype "passive"))
      (node (ref "C11") (pin "1") (pinfunction "1_1") (pintype "passive"))
      (node (ref "C12") (pin "1") (pinfunction "1_1") (pintype "passive"))
      (node (ref "C13") (pin "1") (pinfunction "1_1") (pintype "passive"))
      (node (ref "C14") (pin "1") (pinfunction "1_1") (pintype "passive"))
      (node (ref "C15") (pin "1") (pinfunction "1_1") (pintype "passive"))
      (node (ref "C16") (pin "1") (pinfunction "1_1") (pintype "passive"))
      (node (ref "C17") (pin "1") (pinfunction "1_1") (pintype "passive"))
      (node (ref "C2") (pin "1") (pinfunction "1_1") (pintype "passive"))
      (node (ref "C21") (pin "1") (pinfunction "1_1") (pintype "passive"))
      (node (ref "C22") (pin "1") (pinfunction "1_1") (pintype "passive"))
      (node (ref "C23") (pin "1") (pinfunction "1_1") (pintype "passive"))
      (node (ref "C24") (pin "1") (pinfunction "1_1") (pintype "passive"))
      (node (ref "C3") (pin "1") (pinfunction "1_1") (pintype "passive"))
      (node (ref "C4") (pin "1") (pinfunction "1_1") (pintype "passive"))
      (node (ref "C5") (pin "1") (pinfunction "1_1") (pintype "passive"))
      (node (ref "C6") (pin "1") (pinfunction "1_1") (pintype "passive"))
      (node (ref "C7") (pin "1") (pinfunction "1_1") (pintype "passive"))
      (node (ref "C8") (pin "1") (pinfunction "1_1") (pintype "passive"))
      (node (ref "C9") (pin "1") (pinfunction "1_1") (pintype "passive"))
      (node (ref "D1") (pin "1") (pinfunction "K2_1") (pintype "passive"))
      (node (ref "D12") (pin "1") (pinfunction "1_1") (pintype "power_in"))
      (node (ref "D13") (pin "1") (pinfunction "1_1") (pintype "power_in"))
      (node (ref "D14") (pin "2") (pinfunction "2_2") (pintype "power_in"))
      (node (ref "D2") (pin "1") (pinfunction "K2_1") (pintype "passive"))
      (node (ref "D3") (pin "1") (pinfunction "K2_1") (pintype "passive"))
      (node (ref "D4") (pin "1") (pinfunction "K2_1") (pintype "passive"))
      (node (ref "D5") (pin "1") (pinfunction "K2_1") (pintype "passive"))
      (node (ref "D6") (pin "1") (pinfunction "K2_1") (pintype "passive"))
      (node (ref "J1") (pin "3") (pinfunction "3_3") (pintype "passive"))
      (node (ref "J1") (pin "6") (pinfunction "6_6") (pintype "passive"))
      (node (ref "J2") (pin "11") (pinfunction "11_11") (pintype "passive"))
      (node (ref "J2") (pin "3") (pinfunction "3_3") (pintype "passive"))
      (node (ref "J2") (pin "5") (pinfunction "5_5") (pintype "passive"))
      (node (ref "J2") (pin "S1") (pinfunction "SHIELD1_S1") (pintype "passive"))
      (node (ref "J2") (pin "S2") (pinfunction "SHIELD1_S2") (pintype "passive"))
      (node (ref "J3") (pin "5") (pinfunction "5_5") (pintype "passive"))
      (node (ref "J3") (pin "7") (pinfunction "7_7") (pintype "passive"))
      (node (ref "J3") (pin "S1") (pinfunction "SHIELD1_S1") (pintype "passive"))
      (node (ref "J3") (pin "S2") (pinfunction "SHIELD1_S2") (pintype "passive"))
      (node (ref "J4") (pin "10") (pinfunction "10_10") (pintype "passive"))
      (node (ref "J4") (pin "3") (pinfunction "3_3") (pintype "passive"))
      (node (ref "J4") (pin "4") (pinfunction "4_4") (pintype "passive"))
      (node (ref "J4") (pin "9") (pinfunction "9_9") (pintype "passive"))
      (node (ref "J5") (pin "8") (pinfunction "8_8") (pintype "passive"))
      (node (ref "J7") (pin "3") (pinfunction "3_3") (pintype "passive"))
      (node (ref "LS1") (pin "2") (pinfunction "2_2") (pintype "passive"))
      (node (ref "U1") (pin "12") (pinfunction "VSSA_12") (pintype "power_in"))
      (node (ref "U1") (pin "18") (pinfunction "VSS_18") (pintype "power_in"))
      (node (ref "U1") (pin "60") (pinfunction "BOOT0_60") (pintype "input"))
      (node (ref "U1") (pin "63") (pinfunction "VSS_63") (pintype "power_in"))
      (node (ref "U15") (pin "2") (pinfunction "GND_2") (pintype "power_in"))
      (node (ref "U16") (pin "4") (pinfunction "GND_4") (pintype "passive"))
      (node (ref "U2") (pin "2") (pinfunction "PS_2") (pintype "passive"))
      (node (ref "U2") (pin "3") (pinfunction "GND_3") (pintype "passive"))
      (node (ref "U3") (pin "4") (pinfunction "GND_4") (pintype "passive"))
      (node (ref "U4") (pin "4") (pinfunction "GND_4") (pintype "passive"))
      (node (ref "U5") (pin "10") (pinfunction "GND_10") (pintype "passive"))
      (node (ref "U6") (pin "6") (pinfunction "GND_6") (pintype "power_in"))
      (node (ref "U6") (pin "7") (pinfunction "GND_7") (pintype "power_in"))
      (node (ref "Y1") (pin "1") (pinfunction "NC_1") (pintype "passive"))
      (node (ref "Y1") (pin "2") (pinfunction "GND_2") (pintype "power_in"))
    )
    (net (code "66") (name "Net-(D1-A2)") (class "Default")
      (node (ref "D1") (pin "2") (pinfunction "A2_2") (pintype "passive"))
      (node (ref "R1") (pin "2") (pinfunction "2_2") (pintype "passive"))
    )
    (net (code "67") (name "Net-(D2-A2)") (class "Default")
      (node (ref "D2") (pin "2") (pinfunction "A2_2") (pintype "passive"))
      (node (ref "R2") (pin "2") (pinfunction "2_2") (pintype "passive"))
    )
    (net (code "68") (name "Net-(D3-A2)") (class "Default")
      (node (ref "D3") (pin "2") (pinfunction "A2_2") (pintype "passive"))
      (node (ref "R3") (pin "2") (pinfunction "2_2") (pintype "passive"))
    )
    (net (code "69") (name "Net-(D4-A2)") (class "Default")
      (node (ref "D4") (pin "2") (pinfunction "A2_2") (pintype "passive"))
      (node (ref "R4") (pin "2") (pinfunction "2_2") (pintype "passive"))
    )
    (net (code "70") (name "Net-(D5-A2)") (class "Default")
      (node (ref "D5") (pin "2") (pinfunction "A2_2") (pintype "passive"))
      (node (ref "R5") (pin "2") (pinfunction "2_2") (pintype "passive"))
    )
    (net (code "71") (name "Net-(D6-A2)") (class "Default")
      (node (ref "D6") (pin "2") (pinfunction "A2_2") (pintype "passive"))
      (node (ref "R6") (pin "2") (pinfunction "2_2") (pintype "passive"))
    )
    (net (code "72") (name "Net-(U1B-VCAP_1)") (class "Default")
      (node (ref "C13") (pin "2") (pinfunction "2_2") (pintype "passive"))
      (node (ref "U1") (pin "31") (pinfunction "VCAP_1_31") (pintype "power_in"))
    )
    (net (code "73") (name "Net-(U1B-VCAP_2)") (class "Default")
      (node (ref "C14") (pin "2") (pinfunction "2_2") (pintype "passive"))
      (node (ref "U1") (pin "47") (pinfunction "VCAP_2_47") (pintype "power_in"))
    )
    (net (code "74") (name "Net-(U5-{slash}HOLD_or_{slash}RESET_(IO3))") (class "Default")
      (node (ref "R13") (pin "1") (pinfunction "1_1") (pintype "passive"))
      (node (ref "U5") (pin "1") (pinfunction "/HOLD_or_/RESET_(IO3)_1") (pintype "bidirectional"))
    )
    (net (code "75") (name "Net-(U15-QOD)") (class "Default")
      (node (ref "R12") (pin "1") (pinfunction "1_1") (pintype "passive"))
      (node (ref "U15") (pin "5") (pinfunction "QOD_5") (pintype "power_in"))
    )
    (net (code "76") (name "Net-(Y1-OUT)") (class "Default")
      (node (ref "R8") (pin "2") (pinfunction "2_2") (pintype "passive"))
      (node (ref "Y1") (pin "3") (pinfunction "OUT_3") (pintype "output"))
    )
    (net (code "77") (name "Net-(Y1-VDD)") (class "Default")
      (node (ref "C11") (pin "2") (pinfunction "2_2") (pintype "passive"))
      (node (ref "C12") (pin "2") (pinfunction "2_2") (pintype "passive"))
      (node (ref "R9") (pin "1") (pinfunction "1_1") (pintype "passive"))
      (node (ref "Y1") (pin "4") (pinfunction "VDD_4") (pintype "power_in"))
    )
    (net (code "78") (name "unconnected-(J1-Pad9)") (class "Default")
      (node (ref "J1") (pin "9") (pinfunction "9_9") (pintype "passive+no_connect"))
    )
    (net (code "79") (name "unconnected-(J5-Pad1)") (class "Default")
      (node (ref "J5") (pin "1") (pinfunction "1_1") (pintype "passive+no_connect"))
    )
    (net (code "80") (name "unconnected-(J5-Pad2)") (class "Default")
      (node (ref "J5") (pin "2") (pinfunction "2_2") (pintype "passive+no_connect"))
    )
    (net (code "81") (name "unconnected-(J5-Pad3)") (class "Default")
      (node (ref "J5") (pin "3") (pinfunction "3_3") (pintype "passive+no_connect"))
    )
    (net (code "82") (name "unconnected-(J5-Pad4)") (class "Default")
      (node (ref "J5") (pin "4") (pinfunction "4_4") (pintype "passive+no_connect"))
    )
    (net (code "83") (name "unconnected-(J5-Pad5)") (class "Default")
      (node (ref "J5") (pin "5") (pinfunction "5_5") (pintype "passive+no_connect"))
    )
    (net (code "84") (name "unconnected-(J5-Pad6)") (class "Default")
      (node (ref "J5") (pin "6") (pinfunction "6_6") (pintype "passive+no_connect"))
    )
    (net (code "85") (name "unconnected-(J6-Pad1)") (class "Default")
      (node (ref "J6") (pin "1") (pinfunction "1_1") (pintype "passive+no_connect"))
    )
    (net (code "86") (name "unconnected-(J6-Pad2)") (class "Default")
      (node (ref "J6") (pin "2") (pinfunction "2_2") (pintype "passive+no_connect"))
    )
    (net (code "87") (name "unconnected-(J6-Pad5)") (class "Default")
      (node (ref "J6") (pin "5") (pinfunction "5_5") (pintype "passive+no_connect"))
    )
    (net (code "88") (name "unconnected-(J6-Pad6)") (class "Default")
      (node (ref "J6") (pin "6") (pinfunction "6_6") (pintype "passive+no_connect"))
    )
    (net (code "89") (name "unconnected-(J6-Pad7)") (class "Default")
      (node (ref "J6") (pin "7") (pinfunction "7_7") (pintype "passive+no_connect"))
    )
    (net (code "90") (name "unconnected-(J6-Pad8)") (class "Default")
      (node (ref "J6") (pin "8") (pinfunction "8_8") (pintype "passive+no_connect"))
    )
    (net (code "91") (name "unconnected-(U1B-PA8-Pad41)") (class "Default")
      (node (ref "U1") (pin "41") (pinfunction "PA8_41") (pintype "bidirectional+no_connect"))
    )
    (net (code "92") (name "unconnected-(U1B-PB1-Pad27)") (class "Default")
      (node (ref "U1") (pin "27") (pinfunction "PB1_27") (pintype "bidirectional+no_connect"))
    )
    (net (code "93") (name "unconnected-(U1B-PB2-Pad28)") (class "Default")
      (node (ref "U1") (pin "28") (pinfunction "PB2_28") (pintype "bidirectional+no_connect"))
    )
    (net (code "94") (name "unconnected-(U1B-PB9-Pad62)") (class "Default")
      (node (ref "U1") (pin "62") (pinfunction "PB9_62") (pintype "bidirectional+no_connect"))
    )
    (net (code "95") (name "unconnected-(U1B-PB12-Pad33)") (class "Default")
      (node (ref "U1") (pin "33") (pinfunction "PB12_33") (pintype "bidirectional+no_connect"))
    )
    (net (code "96") (name "unconnected-(U1B-PC4-Pad24)") (class "Default")
      (node (ref "U1") (pin "24") (pinfunction "PC4_24") (pintype "bidirectional+no_connect"))
    )
    (net (code "97") (name "unconnected-(U1B-PC13-Pad2)") (class "Default")
      (node (ref "U1") (pin "2") (pinfunction "PC13_2") (pintype "bidirectional+no_connect"))
    )
    (net (code "98") (name "unconnected-(U1B-PC15{slash}OSC32_OUT-Pad4)") (class "Default")
      (node (ref "U1") (pin "4") (pinfunction "PC15/OSC32_OUT_4") (pintype "bidirectional+no_connect"))
    )
    (net (code "99") (name "unconnected-(U1B-PH1{slash}OSC_OUT-Pad6)") (class "Default")
      (node (ref "U1") (pin "6") (pinfunction "PH1/OSC_OUT_6") (pintype "bidirectional+no_connect"))
    )
    (net (code "100") (name "unconnected-(U5-4-Pad)") (class "Default")
      (node (ref "U5") (pin "") (pinfunction "4_") (pintype "passive+no_connect"))
    )
    (net (code "101") (name "unconnected-(U5-5-Pad)") (class "Default")
      (node (ref "U5") (pin "") (pinfunction "5_") (pintype "passive+no_connect"))
    )
    (net (code "102") (name "unconnected-(U5-6-Pad)") (class "Default")
      (node (ref "U5") (pin "") (pinfunction "6_") (pintype "passive+no_connect"))
    )
    (net (code "103") (name "unconnected-(U5-11-Pad)") (class "Default")
      (node (ref "U5") (pin "") (pinfunction "11_") (pintype "passive+no_connect"))
    )
    (net (code "104") (name "unconnected-(U5-12-Pad)") (class "Default")
      (node (ref "U5") (pin "") (pinfunction "12_") (pintype "passive+no_connect"))
    )
    (net (code "105") (name "unconnected-(U5-13-Pad)") (class "Default")
      (node (ref "U5") (pin "") (pinfunction "13_") (pintype "passive+no_connect"))
    )
    (net (code "106") (name "unconnected-(U5-14-Pad)") (class "Default")
      (node (ref "U5") (pin "") (pinfunction "14_") (pintype "passive+no_connect"))
    )
    (net (code "107") (name "unconnected-(U5-{slash}RESET-Pad3)") (class "Default")
      (node (ref "U5") (pin "3") (pinfunction "/RESET_3") (pintype "passive+no_connect"))
    )
    (net (code "108") (name "unconnected-(U6-NC-Pad10)") (class "Default")
      (node (ref "U6") (pin "10") (pinfunction "NC_10") (pintype "passive+no_connect"))
    )
    (net (code "109") (name "unconnected-(U6-NC-Pad11)") (class "Default")
      (node (ref "U6") (pin "11") (pinfunction "NC_11") (pintype "passive+no_connect"))
    )
    (net (code "110") (name "unconnected-(U15-N_C-Pad4)") (class "Default")
      (node (ref "U15") (pin "4") (pinfunction "N_C_4") (pintype "passive+no_connect"))
    )
  )
)
